# rs485-shield.net
KiCad netlist of a schematic drawn in EAGLE
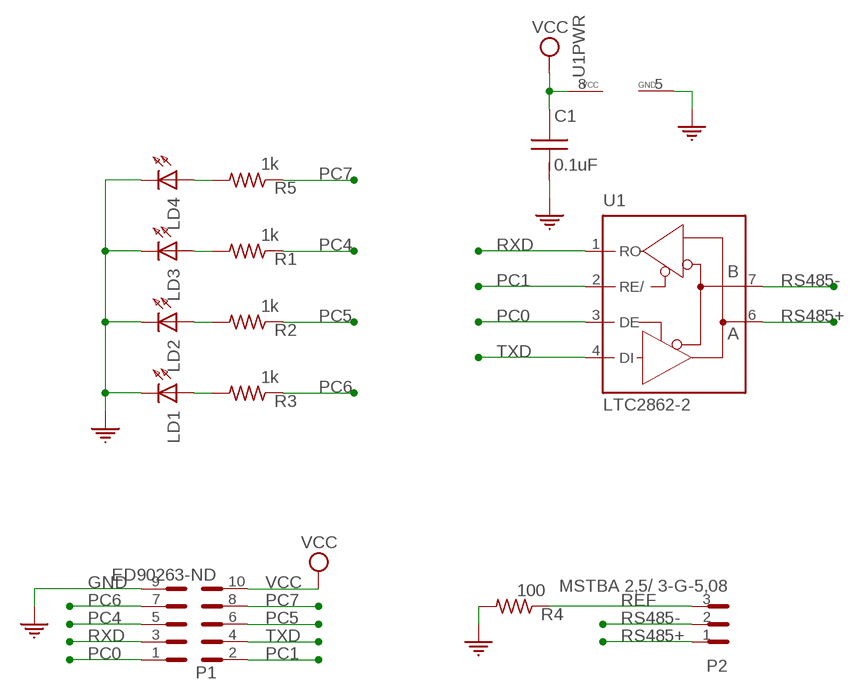
[diagram p0: schematic, sheet 1]

(export (version "E")
  (design (tool "Eeschema 10.0.6"))
  (components
    (comp (ref "C1")
      (value "0.1uF")
      (footprint "eagle-import:C0805")
      (libsource (lib "eagle-import") (part "C-US-0805"))
    )
    (comp (ref "LD1")
      (value "LED-3MM")
      (footprint "eagle-import:LED-3MM")
      (libsource (lib "eagle-import") (part "LED-3MM"))
    )
    (comp (ref "LD2")
      (value "LED-3MM")
      (footprint "eagle-import:LED-3MM")
      (libsource (lib "eagle-import") (part "LED-3MM"))
    )
    (comp (ref "LD3")
      (value "LED-3MM")
      (footprint "eagle-import:LED-3MM")
      (libsource (lib "eagle-import") (part "LED-3MM"))
    )
    (comp (ref "LD4")
      (value "LED-3MM")
      (footprint "eagle-import:LED-3MM")
      (libsource (lib "eagle-import") (part "LED-3MM"))
    )
    (comp (ref "P1")
      (value "ED90263-ND")
      (footprint "eagle-import:PINHD2X5")
      (libsource (lib "eagle-import") (part "PINHEADER2X5-0.1{dblquote}SPACING"))
    )
    (comp (ref "P2")
      (value "MSTBA 2,5/ 3-G-5,08")
      (footprint "eagle-import:CON-MSTBA")
      (libsource (lib "eagle-import") (part "PINHEADER1X3-MSTBA"))
    )
    (comp (ref "R1")
      (value "1k")
      (footprint "eagle-import:RES50_500")
      (libsource (lib "eagle-import") (part "R_?_-RES50/500"))
    )
    (comp (ref "R2")
      (value "1k")
      (footprint "eagle-import:RES50_500")
      (libsource (lib "eagle-import") (part "R_?_-RES50/500"))
    )
    (comp (ref "R3")
      (value "1k")
      (footprint "eagle-import:RES50_500")
      (libsource (lib "eagle-import") (part "R_?_-RES50/500"))
    )
    (comp (ref "R4")
      (value "100")
      (footprint "eagle-import:RES50_500")
      (libsource (lib "eagle-import") (part "R_?_-RES50/500"))
    )
    (comp (ref "R5")
      (value "1k")
      (footprint "eagle-import:RES50_500")
      (libsource (lib "eagle-import") (part "R_?_-RES50/500"))
    )
    (comp (ref "U1")
      (value "LTC2862-2")
      (footprint "eagle-import:SOP08")
      (libsource (lib "eagle-import") (part "RS485-TRANSCEIVER-SOP8"))
    )
  )
  (nets
    (net (code "1") (name "/PC0") (class "Default")
      (node (ref "P1") (pin "1") (pinfunction "1_1") (pintype "bidirectional"))
      (node (ref "U1") (pin "3") (pinfunction "DE_3") (pintype "input"))
    )
    (net (code "2") (name "/PC1") (class "Default")
      (node (ref "P1") (pin "2") (pinfunction "2_2") (pintype "bidirectional"))
      (node (ref "U1") (pin "2") (pinfunction "RE/_2") (pintype "input"))
    )
    (net (code "3") (name "/PC4") (class "Default")
      (node (ref "P1") (pin "5") (pinfunction "5_5") (pintype "bidirectional"))
      (node (ref "R1") (pin "1") (pinfunction "1_1") (pintype "passive"))
    )
    (net (code "4") (name "/PC5") (class "Default")
      (node (ref "P1") (pin "6") (pinfunction "6_6") (pintype "bidirectional"))
      (node (ref "R2") (pin "1") (pinfunction "1_1") (pintype "passive"))
    )
    (net (code "5") (name "/PC6") (class "Default")
      (node (ref "P1") (pin "7") (pinfunction "7_7") (pintype "bidirectional"))
      (node (ref "R3") (pin "1") (pinfunction "1_1") (pintype "passive"))
    )
    (net (code "6") (name "/PC7") (class "Default")
      (node (ref "P1") (pin "8") (pinfunction "8_8") (pintype "bidirectional"))
      (node (ref "R5") (pin "1") (pinfunction "1_1") (pintype "passive"))
    )
    (net (code "7") (name "/REF") (class "Default")
      (node (ref "P2") (pin "3") (pinfunction "3_3") (pintype "passive"))
      (node (ref "R4") (pin "1") (pinfunction "1_1") (pintype "passive"))
    )
    (net (code "8") (name "/RS485+") (class "Default")
      (node (ref "P2") (pin "1") (pinfunction "1_1") (pintype "passive"))
      (node (ref "U1") (pin "6") (pinfunction "A_6") (pintype "passive"))
    )
    (net (code "9") (name "/RS485-") (class "Default")
      (node (ref "P2") (pin "2") (pinfunction "2_2") (pintype "passive"))
      (node (ref "U1") (pin "7") (pinfunction "B_7") (pintype "passive"))
    )
    (net (code "10") (name "/RXD") (class "Default")
      (node (ref "P1") (pin "3") (pinfunction "3_3") (pintype "bidirectional"))
      (node (ref "U1") (pin "1") (pinfunction "RO_1") (pintype "output"))
    )
    (net (code "11") (name "/TXD") (class "Default")
      (node (ref "P1") (pin "4") (pinfunction "4_4") (pintype "bidirectional"))
      (node (ref "U1") (pin "4") (pinfunction "DI_4") (pintype "input"))
    )
    (net (code "12") (name "GND") (class "Default")
      (node (ref "C1") (pin "2") (pinfunction "2_2") (pintype "passive"))
      (node (ref "LD1") (pin "C") (pinfunction "C_C") (pintype "passive"))
      (node (ref "LD2") (pin "C") (pinfunction "C_C") (pintype "passive"))
      (node (ref "LD3") (pin "C") (pinfunction "C_C") (pintype "passive"))
      (node (ref "LD4") (pin "C") (pinfunction "C_C") (pintype "passive"))
      (node (ref "P1") (pin "9") (pinfunction "9_9") (pintype "bidirectional"))
      (node (ref "R4") (pin "2") (pinfunction "2_2") (pintype "passive"))
      (node (ref "U1") (pin "5") (pinfunction "GND_5") (pintype "power_in"))
    )
    (net (code "13") (name "Net-(LD1-PadA)") (class "Default")
      (node (ref "LD1") (pin "A") (pinfunction "A_A") (pintype "passive"))
      (node (ref "R3") (pin "2") (pinfunction "2_2") (pintype "passive"))
    )
    (net (code "14") (name "Net-(LD2-PadA)") (class "Default")
      (node (ref "LD2") (pin "A") (pinfunction "A_A") (pintype "passive"))
      (node (ref "R2") (pin "2") (pinfunction "2_2") (pintype "passive"))
    )
    (net (code "15") (name "Net-(LD3-PadA)") (class "Default")
      (node (ref "LD3") (pin "A") (pinfunction "A_A") (pintype "passive"))
      (node (ref "R1") (pin "2") (pinfunction "2_2") (pintype "passive"))
    )
    (net (code "16") (name "Net-(LD4-PadA)") (class "Default")
      (node (ref "LD4") (pin "A") (pinfunction "A_A") (pintype "passive"))
      (node (ref "R5") (pin "2") (pinfunction "2_2") (pintype "passive"))
    )
    (net (code "17") (name "VCC") (class "Default")
      (node (ref "C1") (pin "1") (pinfunction "1_1") (pintype "passive"))
      (node (ref "P1") (pin "10") (pinfunction "10_10") (pintype "bidirectional"))
      (node (ref "U1") (pin "8") (pinfunction "VCC_8") (pintype "power_in"))
    )
  )
)
